# control-boardv1_0.net
KiCad netlist of a schematic drawn in Altium Designer
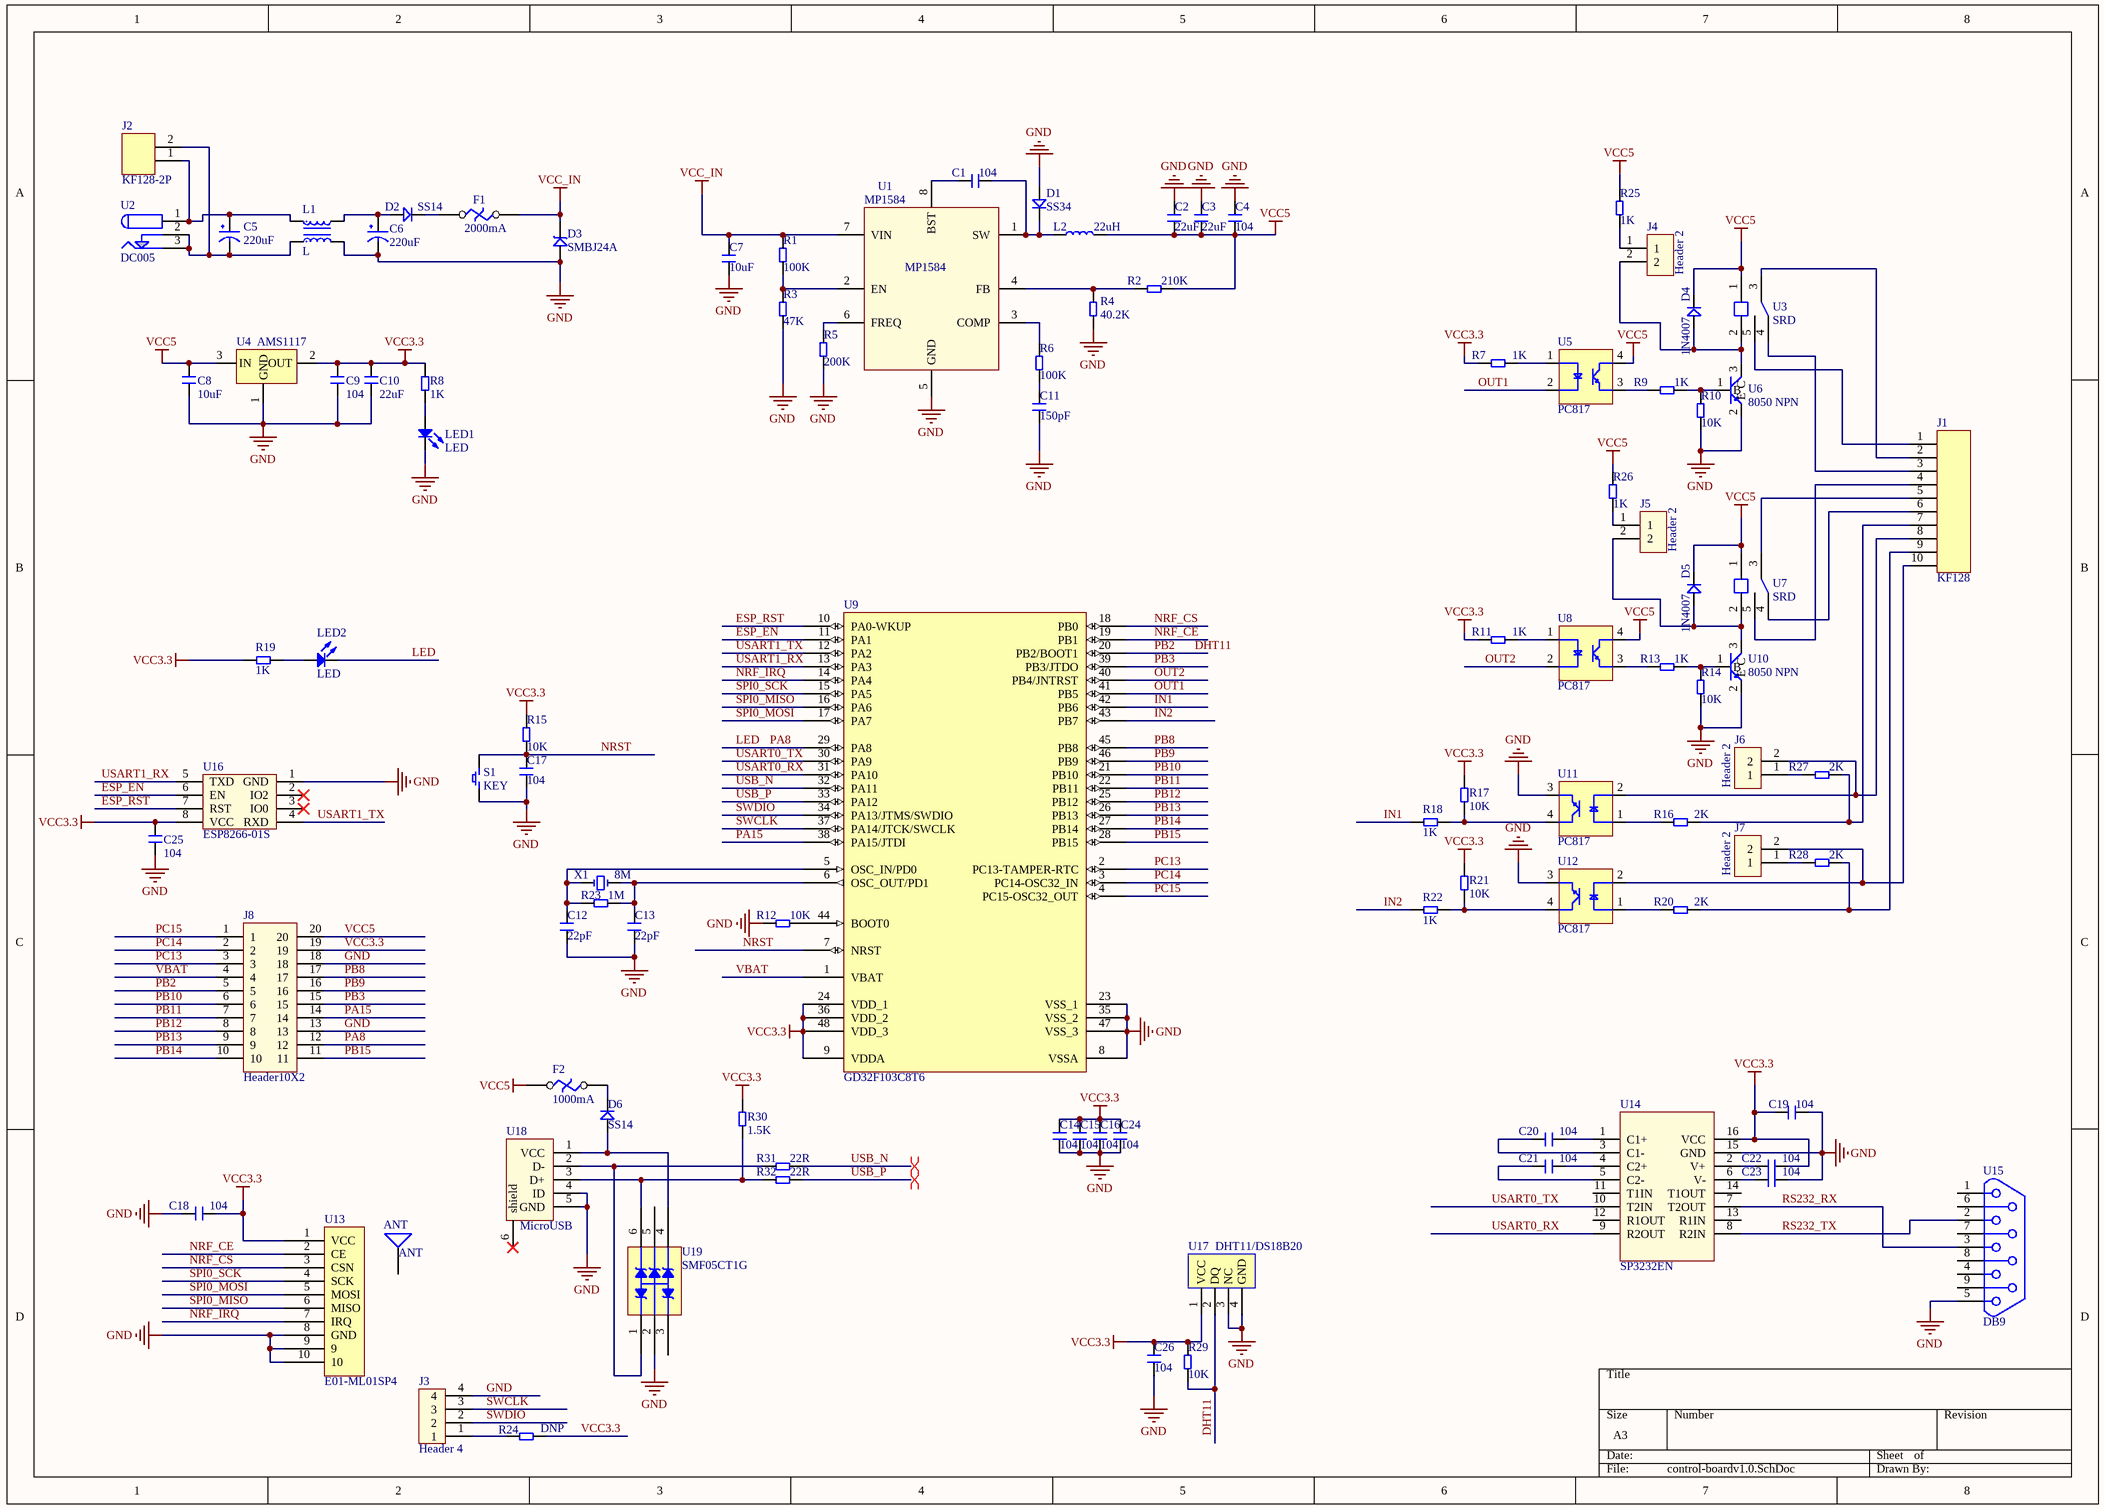
[diagram p0: control-boardv1.0.SchDoc]

(export (version "E")
  (design (tool "Eeschema 10.0.6"))
  (components
    (comp (ref "ANT") (value "ANT") (footprint "ANT-SMA-FR") (libsource (lib "squ-guiboard") (part "ANT")))
    (comp (ref "C1") (value "104") (footprint "C 0603") (libsource (lib "squ-guiboard") (part "CAP")))
    (comp (ref "C2") (value "22uF") (footprint "C 0805") (libsource (lib "squ-guiboard") (part "CAP")))
    (comp (ref "C3") (value "22uF") (footprint "C 0805") (libsource (lib "squ-guiboard") (part "CAP")))
    (comp (ref "C4") (value "104") (footprint "C 0603") (libsource (lib "squ-guiboard") (part "CAP")))
    (comp (ref "C5")
      (value "220uF")
      (footprint "CS 3.5*8*11.5 - C")
      (description "极性电容")
      (libsource (lib "squ-guiboard") (part "CAP Pol"))
    )
    (comp (ref "C6")
      (value "220uF")
      (footprint "CS 3.5*8*11.5 - C")
      (description "极性电容")
      (libsource (lib "squ-guiboard") (part "CAP Pol"))
    )
    (comp (ref "C7") (value "10uF") (footprint "C 0805") (libsource (lib "squ-guiboard") (part "CAP")))
    (comp (ref "C8") (value "10uF") (footprint "C 0805") (libsource (lib "squ-guiboard") (part "CAP")))
    (comp (ref "C9") (value "104") (footprint "C 0603") (libsource (lib "squ-guiboard") (part "CAP")))
    (comp (ref "C10") (value "22uF") (footprint "C 0805") (libsource (lib "squ-guiboard") (part "CAP")))
    (comp (ref "C11") (value "150pF") (footprint "C 0603") (libsource (lib "squ-guiboard") (part "CAP")))
    (comp (ref "C12") (value "22pF") (footprint "C 0603") (libsource (lib "squ-guiboard") (part "CAP")))
    (comp (ref "C13") (value "22pF") (footprint "C 0603") (libsource (lib "squ-guiboard") (part "CAP")))
    (comp (ref "C14") (value "104") (footprint "C 0603") (libsource (lib "squ-guiboard") (part "CAP")))
    (comp (ref "C15") (value "104") (footprint "C 0603") (libsource (lib "squ-guiboard") (part "CAP")))
    (comp (ref "C16") (value "104") (footprint "C 0603") (libsource (lib "squ-guiboard") (part "CAP")))
    (comp (ref "C17") (value "104") (footprint "C 0603") (libsource (lib "squ-guiboard") (part "CAP")))
    (comp (ref "C18") (value "104") (footprint "C 0603") (libsource (lib "squ-guiboard") (part "CAP")))
    (comp (ref "C19") (value "104") (footprint "C 0603") (libsource (lib "squ-guiboard") (part "CAP")))
    (comp (ref "C20") (value "104") (footprint "C 0603") (libsource (lib "squ-guiboard") (part "CAP")))
    (comp (ref "C21") (value "104") (footprint "C 0603") (libsource (lib "squ-guiboard") (part "CAP")))
    (comp (ref "C22") (value "104") (footprint "C 0603") (libsource (lib "squ-guiboard") (part "CAP")))
    (comp (ref "C23") (value "104") (footprint "C 0603") (libsource (lib "squ-guiboard") (part "CAP")))
    (comp (ref "C24") (value "104") (footprint "C 0603") (libsource (lib "squ-guiboard") (part "CAP")))
    (comp (ref "C25") (value "104") (footprint "C 0603") (libsource (lib "squ-guiboard") (part "CAP")))
    (comp (ref "C26") (value "104") (footprint "C 0603") (libsource (lib "squ-guiboard") (part "CAP")))
    (comp (ref "D1") (value "SS34") (footprint "SMA") (libsource (lib "squ-guiboard") (part "Diode")))
    (comp (ref "D2") (value "SS14") (footprint "SMA") (libsource (lib "squ-guiboard") (part "Diode")))
    (comp (ref "D3") (value "SMBJ24A") (footprint "SMA") (libsource (lib "squ-guiboard") (part "D Schottky")))
    (comp (ref "D4") (value "1N4007") (footprint "LL34") (libsource (lib "squ-guiboard") (part "Diode")))
    (comp (ref "D5") (value "1N4007") (footprint "LL34") (libsource (lib "squ-guiboard") (part "Diode")))
    (comp (ref "D6") (value "SS14") (footprint "SMA") (libsource (lib "squ-guiboard") (part "Diode")))
    (comp (ref "F1")
      (value "2000mA")
      (footprint "F 1206")
      (description "熔断开关")
      (libsource (lib "squ-guiboard") (part "F"))
    )
    (comp (ref "F2")
      (value "1000mA")
      (footprint "F 1206")
      (description "熔断开关")
      (libsource (lib "squ-guiboard") (part "F"))
    )
    (comp (ref "J1")
      (value "KF128")
      (footprint "KF128-5.08-10P")
      (libsource (lib "squ-guiboard") (part "KF128-10P"))
    )
    (comp (ref "J2")
      (value "KF128-2P")
      (footprint "KF128-5.08-2P")
      (libsource (lib "squ-guiboard") (part "KF128-2P"))
    )
    (comp (ref "J3")
      (value "Header 4")
      (footprint "XH2.54-LI-4P")
      (libsource (lib "squ-guiboard") (part "Header 4"))
    )
    (comp (ref "J4")
      (value "Header 2")
      (footprint "XH2.54-LI-2P")
      (libsource (lib "squ-guiboard") (part "Header 2"))
    )
    (comp (ref "J5")
      (value "Header 2")
      (footprint "XH2.54-LI-2P")
      (libsource (lib "squ-guiboard") (part "Header 2"))
    )
    (comp (ref "J6") (value "Header 2") (footprint "XH2.54-LI-2P") (libsource (lib "") (part "Header 2_1")))
    (comp (ref "J7") (value "Header 2") (footprint "XH2.54-LI-2P") (libsource (lib "") (part "Header 2_1")))
    (comp (ref "J8")
      (value "Header10X2")
      (footprint "HDR2.54-LI-2x10P")
      (libsource (lib "squ-guiboard") (part "Header10X2"))
    )
    (comp (ref "L1") (value "L") (footprint "L UU9.8") (libsource (lib "squ-guiboard") (part "L2")))
    (comp (ref "L2") (value "22uH") (footprint "L CDRH74") (libsource (lib "squ-guiboard") (part "L")))
    (comp (ref "LED1") (value "LED") (footprint "LED 3MM") (libsource (lib "squ-guiboard") (part "LED")))
    (comp (ref "LED2") (value "LED") (footprint "LED 3MM") (libsource (lib "squ-guiboard") (part "LED")))
    (comp (ref "R1") (value "100K") (footprint "R 0603") (libsource (lib "squ-guiboard") (part "RES")))
    (comp (ref "R2") (value "210K") (footprint "R 0603") (libsource (lib "squ-guiboard") (part "RES")))
    (comp (ref "R3") (value "47K") (footprint "R 0603") (libsource (lib "squ-guiboard") (part "RES")))
    (comp (ref "R4") (value "40.2K") (footprint "R 0603") (libsource (lib "squ-guiboard") (part "RES")))
    (comp (ref "R5") (value "200K") (footprint "R 0603") (libsource (lib "squ-guiboard") (part "RES")))
    (comp (ref "R6") (value "100K") (footprint "R 0603") (libsource (lib "squ-guiboard") (part "RES")))
    (comp (ref "R7") (value "1K") (footprint "R 0603") (libsource (lib "squ-guiboard") (part "RES")))
    (comp (ref "R8") (value "1K") (footprint "R 0603") (libsource (lib "squ-guiboard") (part "RES")))
    (comp (ref "R9") (value "1K") (footprint "R 0603") (libsource (lib "squ-guiboard") (part "RES")))
    (comp (ref "R10") (value "10K") (footprint "R 0603") (libsource (lib "squ-guiboard") (part "RES")))
    (comp (ref "R11") (value "1K") (footprint "R 0603") (libsource (lib "squ-guiboard") (part "RES")))
    (comp (ref "R12") (value "10K") (footprint "R 0603") (libsource (lib "squ-guiboard") (part "RES")))
    (comp (ref "R13") (value "1K") (footprint "R 0603") (libsource (lib "squ-guiboard") (part "RES")))
    (comp (ref "R14") (value "10K") (footprint "R 0603") (libsource (lib "squ-guiboard") (part "RES")))
    (comp (ref "R15") (value "10K") (footprint "R 0603") (libsource (lib "squ-guiboard") (part "RES")))
    (comp (ref "R16") (value "2K") (footprint "R 0603") (libsource (lib "squ-guiboard") (part "RES")))
    (comp (ref "R17") (value "10K") (footprint "R 0603") (libsource (lib "squ-guiboard") (part "RES")))
    (comp (ref "R18") (value "1K") (footprint "R 0603") (libsource (lib "squ-guiboard") (part "RES")))
    (comp (ref "R19") (value "1K") (footprint "R 0603") (libsource (lib "squ-guiboard") (part "RES")))
    (comp (ref "R20") (value "2K") (footprint "R 0603") (libsource (lib "squ-guiboard") (part "RES")))
    (comp (ref "R21") (value "10K") (footprint "R 0603") (libsource (lib "squ-guiboard") (part "RES")))
    (comp (ref "R22") (value "1K") (footprint "R 0603") (libsource (lib "squ-guiboard") (part "RES")))
    (comp (ref "R23") (value "1M") (footprint "R 0603") (libsource (lib "squ-guiboard") (part "RES")))
    (comp (ref "R24") (value "DNP") (footprint "R 0603") (libsource (lib "松鼠GUI原理图库") (part "RES")))
    (comp (ref "R25") (value "1K") (footprint "R 0603") (libsource (lib "squ-guiboard") (part "RES")))
    (comp (ref "R26") (value "1K") (footprint "R 0603") (libsource (lib "squ-guiboard") (part "RES")))
    (comp (ref "R27") (value "2K") (footprint "R 0603") (libsource (lib "squ-guiboard") (part "RES")))
    (comp (ref "R28") (value "2K") (footprint "R 0603") (libsource (lib "squ-guiboard") (part "RES")))
    (comp (ref "R29") (value "10K") (footprint "R 0603") (libsource (lib "squ-guiboard") (part "RES")))
    (comp (ref "R30") (value "1.5K") (footprint "R 0603") (libsource (lib "squ-guiboard") (part "RES")))
    (comp (ref "R31") (value "22R") (footprint "R 0603") (libsource (lib "squ-guiboard") (part "RES")))
    (comp (ref "R32") (value "22R") (footprint "R 0603") (libsource (lib "squ-guiboard") (part "RES")))
    (comp (ref "S1")
      (value "KEY")
      (footprint "KEY SMD-3*6*2.5")
      (libsource (lib "squ-guiboard") (part "KEY"))
    )
    (comp (ref "U1")
      (value "MP1584")
      (footprint "MP1584 SOP8")
      (description "DCDC芯片")
      (libsource (lib "squ-guiboard") (part "MP1584"))
    )
    (comp (ref "U2") (value "DC005") (footprint "DC005") (libsource (lib "squ-guiboard") (part "DC005")))
    (comp (ref "U3")
      (value "SRD")
      (footprint "SRD-C")
      (description "继电器")
      (libsource (lib "squ-guiboard") (part "SRD"))
    )
    (comp (ref "U4")
      (value "AMS1117")
      (footprint "SOT223")
      (description "LDO")
      (libsource (lib "squ-guiboard") (part "AMS1117"))
    )
    (comp (ref "U5")
      (value "PC817")
      (footprint "DIP4")
      (description "光耦")
      (libsource (lib "") (part "PC817_1"))
    )
    (comp (ref "U6") (value "8050 NPN") (footprint "SOT23-3") (libsource (lib "squ-guiboard") (part "NPN")))
    (comp (ref "U7")
      (value "SRD")
      (footprint "SRD-C")
      (description "继电器")
      (libsource (lib "squ-guiboard") (part "SRD"))
    )
    (comp (ref "U8")
      (value "PC817")
      (footprint "DIP4")
      (description "光耦")
      (libsource (lib "") (part "PC817_1"))
    )
    (comp (ref "U9")
      (value "GD32F103C8T6")
      (footprint "LQFP48")
      (libsource (lib "squ-guiboard") (part "GD32F103C8T6"))
    )
    (comp (ref "U10") (value "8050 NPN") (footprint "SOT23-3") (libsource (lib "squ-guiboard") (part "NPN")))
    (comp (ref "U11")
      (value "PC817")
      (footprint "DIP4")
      (description "光耦")
      (libsource (lib "squ-guiboard") (part "PC817"))
    )
    (comp (ref "U12")
      (value "PC817")
      (footprint "DIP4")
      (description "光耦")
      (libsource (lib "squ-guiboard") (part "PC817"))
    )
    (comp (ref "U13")
      (value "E01-ML01SP4")
      (footprint "E01-ML01SP4")
      (description "2.4G无限模块")
      (libsource (lib "squ-guiboard") (part "24L01"))
    )
    (comp (ref "U14")
      (value "SP3232EN")
      (footprint "TSSOP16")
      (libsource (lib "squ-guiboard") (part "SP3232EN"))
    )
    (comp (ref "U15") (value "DB9") (footprint "DB9-MALE") (libsource (lib "squ-guiboard") (part "DB9")))
    (comp (ref "U16")
      (value "ESP8266-01S")
      (footprint "ESP8266-01S")
      (description "WIFI模块")
      (libsource (lib "squ-guiboard") (part "ESP8266-01S"))
    )
    (comp (ref "U17")
      (value "DHT11/DS18B20")
      (footprint "DHT11")
      (libsource (lib "squ-guiboard") (part "DHT11"))
    )
    (comp (ref "U18")
      (value "MicroUSB")
      (footprint "USB MICROUSB-L")
      (libsource (lib "squ-guiboard") (part "MicroUSB"))
    )
    (comp (ref "U19")
      (value "SMF05CT1G")
      (footprint "LC-SC-70-6(SOT-363)")
      (description "TVS")
      (libsource (lib "Miscellaneous Devices LC") (part "SMF05CT1G"))
    )
    (comp (ref "X1") (value "8M") (footprint "XTAL-HC49S") (libsource (lib "squ-guiboard") (part "XTAL-2P")))
  )
  (nets
    (net (code "1") (name "/DHT11") (class "Default")
      (node (ref "J8") (pin "5") (pinfunction "5_5") (pintype "passive"))
      (node (ref "R29") (pin "1") (pintype "passive"))
      (node (ref "U17") (pin "2") (pinfunction "DQ_2") (pintype "passive"))
      (node (ref "U9") (pin "20") (pinfunction "PB2/BOOT1_20") (pintype "bidirectional"))
    )
    (net (code "2") (name "/ESP_EN") (class "Default")
      (node (ref "U16") (pin "6") (pinfunction "EN_6") (pintype "passive"))
      (node (ref "U9") (pin "11") (pinfunction "PA1_11") (pintype "bidirectional"))
    )
    (net (code "3") (name "/ESP_RST") (class "Default")
      (node (ref "U16") (pin "7") (pinfunction "RST_7") (pintype "passive"))
      (node (ref "U9") (pin "10") (pinfunction "PA0-WKUP_10") (pintype "bidirectional"))
    )
    (net (code "4") (name "/IN1") (class "Default")
      (node (ref "R18") (pin "1") (pintype "passive"))
      (node (ref "U9") (pin "42") (pinfunction "PB6_42") (pintype "bidirectional"))
    )
    (net (code "5") (name "/IN2") (class "Default")
      (node (ref "R22") (pin "1") (pintype "passive"))
      (node (ref "U9") (pin "43") (pinfunction "PB7_43") (pintype "bidirectional"))
    )
    (net (code "6") (name "/LED") (class "Default")
      (node (ref "J8") (pin "12") (pinfunction "12_12") (pintype "passive"))
      (node (ref "LED2") (pin "2") (pinfunction "K_2") (pintype "passive"))
      (node (ref "U9") (pin "29") (pinfunction "PA8_29") (pintype "bidirectional"))
    )
    (net (code "7") (name "/NRF_CE") (class "Default")
      (node (ref "U13") (pin "2") (pinfunction "CE_2") (pintype "passive"))
      (node (ref "U9") (pin "19") (pinfunction "PB1_19") (pintype "bidirectional"))
    )
    (net (code "8") (name "/NRF_CS") (class "Default")
      (node (ref "U13") (pin "3") (pinfunction "CSN_3") (pintype "passive"))
      (node (ref "U9") (pin "18") (pinfunction "PB0_18") (pintype "bidirectional"))
    )
    (net (code "9") (name "/NRF_IRQ") (class "Default")
      (node (ref "U13") (pin "7") (pinfunction "IRQ_7") (pintype "passive"))
      (node (ref "U9") (pin "14") (pinfunction "PA4_14") (pintype "bidirectional"))
    )
    (net (code "10") (name "/NRST") (class "Default")
      (node (ref "C17") (pin "2") (pinfunction "2_2") (pintype "passive"))
      (node (ref "R15") (pin "1") (pintype "passive"))
      (node (ref "S1") (pin "2") (pinfunction "2_2") (pintype "passive"))
      (node (ref "U9") (pin "7") (pinfunction "NRST_7") (pintype "bidirectional"))
    )
    (net (code "11") (name "/OUT1") (class "Default")
      (node (ref "U5") (pin "2") (pinfunction "2_2") (pintype "passive"))
      (node (ref "U9") (pin "41") (pinfunction "PB5_41") (pintype "bidirectional"))
    )
    (net (code "12") (name "/OUT2") (class "Default")
      (node (ref "U8") (pin "2") (pinfunction "2_2") (pintype "passive"))
      (node (ref "U9") (pin "40") (pinfunction "PB4/JNTRST_40") (pintype "bidirectional"))
    )
    (net (code "13") (name "/PA15") (class "Default")
      (node (ref "J8") (pin "14") (pinfunction "14_14") (pintype "passive"))
      (node (ref "U9") (pin "38") (pinfunction "PA15/JTDI_38") (pintype "bidirectional"))
    )
    (net (code "14") (name "/PB3") (class "Default")
      (node (ref "J8") (pin "15") (pinfunction "15_15") (pintype "passive"))
      (node (ref "U9") (pin "39") (pinfunction "PB3/JTDO_39") (pintype "bidirectional"))
    )
    (net (code "15") (name "/PB8") (class "Default")
      (node (ref "J8") (pin "17") (pinfunction "17_17") (pintype "passive"))
      (node (ref "U9") (pin "45") (pinfunction "PB8_45") (pintype "bidirectional"))
    )
    (net (code "16") (name "/PB9") (class "Default")
      (node (ref "J8") (pin "16") (pinfunction "16_16") (pintype "passive"))
      (node (ref "U9") (pin "46") (pinfunction "PB9_46") (pintype "bidirectional"))
    )
    (net (code "17") (name "/PB10") (class "Default")
      (node (ref "J8") (pin "6") (pinfunction "6_6") (pintype "passive"))
      (node (ref "U9") (pin "21") (pinfunction "PB10_21") (pintype "bidirectional"))
    )
    (net (code "18") (name "/PB11") (class "Default")
      (node (ref "J8") (pin "7") (pinfunction "7_7") (pintype "passive"))
      (node (ref "U9") (pin "22") (pinfunction "PB11_22") (pintype "bidirectional"))
    )
    (net (code "19") (name "/PB12") (class "Default")
      (node (ref "J8") (pin "8") (pinfunction "8_8") (pintype "passive"))
      (node (ref "U9") (pin "25") (pinfunction "PB12_25") (pintype "bidirectional"))
    )
    (net (code "20") (name "/PB13") (class "Default")
      (node (ref "J8") (pin "9") (pinfunction "9_9") (pintype "passive"))
      (node (ref "U9") (pin "26") (pinfunction "PB13_26") (pintype "bidirectional"))
    )
    (net (code "21") (name "/PB14") (class "Default")
      (node (ref "J8") (pin "10") (pinfunction "10_10") (pintype "passive"))
      (node (ref "U9") (pin "27") (pinfunction "PB14_27") (pintype "bidirectional"))
    )
    (net (code "22") (name "/PB15") (class "Default")
      (node (ref "J8") (pin "11") (pinfunction "11_11") (pintype "passive"))
      (node (ref "U9") (pin "28") (pinfunction "PB15_28") (pintype "bidirectional"))
    )
    (net (code "23") (name "/PC13") (class "Default")
      (node (ref "J8") (pin "3") (pinfunction "3_3") (pintype "passive"))
      (node (ref "U9") (pin "2") (pinfunction "PC13-TAMPER-RTC_2") (pintype "bidirectional"))
    )
    (net (code "24") (name "/PC14") (class "Default")
      (node (ref "J8") (pin "2") (pinfunction "2_2") (pintype "passive"))
      (node (ref "U9") (pin "3") (pinfunction "PC14-OSC32_IN_3") (pintype "bidirectional"))
    )
    (net (code "25") (name "/PC15") (class "Default")
      (node (ref "J8") (pin "1") (pinfunction "1_1") (pintype "passive"))
      (node (ref "U9") (pin "4") (pinfunction "PC15-OSC32_OUT_4") (pintype "bidirectional"))
    )
    (net (code "26") (name "/RS232_RX") (class "Default")
      (node (ref "U14") (pin "7") (pinfunction "T2OUT_7") (pintype "passive"))
      (node (ref "U15") (pin "3") (pinfunction "3_3") (pintype "passive"))
    )
    (net (code "27") (name "/RS232_TX") (class "Default")
      (node (ref "U14") (pin "8") (pinfunction "R2IN_8") (pintype "passive"))
      (node (ref "U15") (pin "2") (pinfunction "2_2") (pintype "passive"))
    )
    (net (code "28") (name "/SPI0_MISO") (class "Default")
      (node (ref "U13") (pin "6") (pinfunction "MISO_6") (pintype "passive"))
      (node (ref "U9") (pin "16") (pinfunction "PA6_16") (pintype "bidirectional"))
    )
    (net (code "29") (name "/SPI0_MOSI") (class "Default")
      (node (ref "U13") (pin "5") (pinfunction "MOSI_5") (pintype "passive"))
      (node (ref "U9") (pin "17") (pinfunction "PA7_17") (pintype "bidirectional"))
    )
    (net (code "30") (name "/SPI0_SCK") (class "Default")
      (node (ref "U13") (pin "4") (pinfunction "SCK_4") (pintype "passive"))
      (node (ref "U9") (pin "15") (pinfunction "PA5_15") (pintype "bidirectional"))
    )
    (net (code "31") (name "/SWCLK") (class "Default")
      (node (ref "J3") (pin "3") (pinfunction "3_3") (pintype "passive"))
      (node (ref "U9") (pin "37") (pinfunction "PA14/JTCK/SWCLK_37") (pintype "bidirectional"))
    )
    (net (code "32") (name "/SWDIO") (class "Default")
      (node (ref "J3") (pin "2") (pinfunction "2_2") (pintype "passive"))
      (node (ref "U9") (pin "34") (pinfunction "PA13/JTMS/SWDIO_34") (pintype "bidirectional"))
    )
    (net (code "33") (name "/USART0_RX") (class "Default")
      (node (ref "U14") (pin "9") (pinfunction "R2OUT_9") (pintype "passive"))
      (node (ref "U9") (pin "31") (pinfunction "PA10_31") (pintype "bidirectional"))
    )
    (net (code "34") (name "/USART0_TX") (class "Default")
      (node (ref "U14") (pin "10") (pinfunction "T2IN_10") (pintype "passive"))
      (node (ref "U9") (pin "30") (pinfunction "PA9_30") (pintype "bidirectional"))
    )
    (net (code "35") (name "/USART1_RX") (class "Default")
      (node (ref "U16") (pin "5") (pinfunction "TXD_5") (pintype "passive"))
      (node (ref "U9") (pin "13") (pinfunction "PA3_13") (pintype "bidirectional"))
    )
    (net (code "36") (name "/USART1_TX") (class "Default")
      (node (ref "U16") (pin "4") (pinfunction "RXD_4") (pintype "passive"))
      (node (ref "U9") (pin "12") (pinfunction "PA2_12") (pintype "bidirectional"))
    )
    (net (code "37") (name "/USB_N") (class "Default")
      (node (ref "R31") (pin "2") (pintype "passive"))
      (node (ref "U9") (pin "32") (pinfunction "PA11_32") (pintype "bidirectional"))
    )
    (net (code "38") (name "/USB_P") (class "Default")
      (node (ref "R32") (pin "2") (pintype "passive"))
      (node (ref "U9") (pin "33") (pinfunction "PA12_33") (pintype "bidirectional"))
    )
    (net (code "39") (name "/VBAT") (class "Default")
      (node (ref "J8") (pin "4") (pinfunction "4_4") (pintype "passive"))
      (node (ref "U9") (pin "1") (pinfunction "VBAT_1") (pintype "power_in"))
    )
    (net (code "40") (name "GND") (class "Default")
      (node (ref "C10") (pin "1") (pinfunction "1_1") (pintype "passive"))
      (node (ref "C11") (pin "1") (pinfunction "1_1") (pintype "passive"))
      (node (ref "C12") (pin "1") (pinfunction "1_1") (pintype "passive"))
      (node (ref "C13") (pin "1") (pinfunction "1_1") (pintype "passive"))
      (node (ref "C14") (pin "1") (pinfunction "1_1") (pintype "passive"))
      (node (ref "C15") (pin "1") (pinfunction "1_1") (pintype "passive"))
      (node (ref "C16") (pin "1") (pinfunction "1_1") (pintype "passive"))
      (node (ref "C17") (pin "1") (pinfunction "1_1") (pintype "passive"))
      (node (ref "C18") (pin "2") (pinfunction "2_2") (pintype "passive"))
      (node (ref "C19") (pin "1") (pinfunction "1_1") (pintype "passive"))
      (node (ref "C2") (pin "2") (pinfunction "2_2") (pintype "passive"))
      (node (ref "C23") (pin "2") (pinfunction "2_2") (pintype "passive"))
      (node (ref "C24") (pin "1") (pinfunction "1_1") (pintype "passive"))
      (node (ref "C25") (pin "2") (pinfunction "2_2") (pintype "passive"))
      (node (ref "C26") (pin "2") (pinfunction "2_2") (pintype "passive"))
      (node (ref "C3") (pin "2") (pinfunction "2_2") (pintype "passive"))
      (node (ref "C4") (pin "2") (pinfunction "2_2") (pintype "passive"))
      (node (ref "C6") (pin "2") (pinfunction "-_2") (pintype "passive"))
      (node (ref "C7") (pin "1") (pinfunction "1_1") (pintype "passive"))
      (node (ref "C8") (pin "1") (pinfunction "1_1") (pintype "passive"))
      (node (ref "C9") (pin "1") (pinfunction "1_1") (pintype "passive"))
      (node (ref "D1") (pin "1") (pintype "passive"))
      (node (ref "D3") (pin "1") (pintype "passive"))
      (node (ref "J3") (pin "4") (pinfunction "4_4") (pintype "passive"))
      (node (ref "J8") (pin "13") (pinfunction "13_13") (pintype "passive"))
      (node (ref "J8") (pin "18") (pinfunction "18_18") (pintype "passive"))
      (node (ref "L1") (pin "3") (pinfunction "3_3") (pintype "passive"))
      (node (ref "LED1") (pin "2") (pinfunction "K_2") (pintype "passive"))
      (node (ref "R10") (pin "1") (pintype "passive"))
      (node (ref "R12") (pin "1") (pintype "passive"))
      (node (ref "R14") (pin "1") (pintype "passive"))
      (node (ref "R3") (pin "1") (pintype "passive"))
      (node (ref "R4") (pin "1") (pintype "passive"))
      (node (ref "R5") (pin "1") (pintype "passive"))
      (node (ref "S1") (pin "1") (pinfunction "1_1") (pintype "passive"))
      (node (ref "U1") (pin "5") (pinfunction "GND_5") (pintype "passive"))
      (node (ref "U10") (pin "2") (pinfunction "E_2") (pintype "passive"))
      (node (ref "U11") (pin "3") (pinfunction "3_3") (pintype "passive"))
      (node (ref "U12") (pin "3") (pinfunction "3_3") (pintype "passive"))
      (node (ref "U13") (pin "10") (pinfunction "10_10") (pintype "passive"))
      (node (ref "U13") (pin "8") (pinfunction "GND_8") (pintype "passive"))
      (node (ref "U13") (pin "9") (pinfunction "9_9") (pintype "passive"))
      (node (ref "U14") (pin "15") (pinfunction "GND_15") (pintype "passive"))
      (node (ref "U15") (pin "5") (pinfunction "5_5") (pintype "passive"))
      (node (ref "U16") (pin "1") (pinfunction "GND_1") (pintype "passive"))
      (node (ref "U17") (pin "3") (pinfunction "NC_3") (pintype "passive"))
      (node (ref "U17") (pin "4") (pinfunction "GND_4") (pintype "passive"))
      (node (ref "U18") (pin "4") (pinfunction "ID_4") (pintype "passive"))
      (node (ref "U18") (pin "5") (pinfunction "GND_5") (pintype "passive"))
      (node (ref "U19") (pin "2") (pinfunction "2_2") (pintype "passive"))
      (node (ref "U4") (pin "1") (pinfunction "GND_1") (pintype "passive"))
      (node (ref "U6") (pin "2") (pinfunction "E_2") (pintype "passive"))
      (node (ref "U9") (pin "23") (pinfunction "VSS_1_23") (pintype "power_in"))
      (node (ref "U9") (pin "35") (pinfunction "VSS_2_35") (pintype "power_in"))
      (node (ref "U9") (pin "47") (pinfunction "VSS_3_47") (pintype "power_in"))
      (node (ref "U9") (pin "8") (pinfunction "VSSA_8") (pintype "power_in"))
    )
    (net (code "41") (name "Net-(C5-+)") (class "Default")
      (node (ref "C5") (pin "1") (pinfunction "+_1") (pintype "passive"))
      (node (ref "J2") (pin "1") (pinfunction "1_1") (pintype "passive"))
      (node (ref "L1") (pin "1") (pinfunction "1_1") (pintype "passive"))
      (node (ref "U2") (pin "1") (pintype "passive"))
    )
    (net (code "42") (name "Net-(C5--)") (class "Default")
      (node (ref "C5") (pin "2") (pinfunction "-_2") (pintype "passive"))
      (node (ref "J2") (pin "2") (pinfunction "2_2") (pintype "passive"))
      (node (ref "L1") (pin "4") (pinfunction "4_4") (pintype "passive"))
      (node (ref "U2") (pin "2") (pintype "passive"))
      (node (ref "U2") (pin "3") (pintype "passive"))
    )
    (net (code "43") (name "Net-(C6-+)") (class "Default")
      (node (ref "C6") (pin "1") (pinfunction "+_1") (pintype "passive"))
      (node (ref "D2") (pin "1") (pintype "passive"))
      (node (ref "L1") (pin "2") (pinfunction "2_2") (pintype "passive"))
    )
    (net (code "44") (name "Net-(C11-Pad2)") (class "Default")
      (node (ref "C11") (pin "2") (pinfunction "2_2") (pintype "passive"))
      (node (ref "R6") (pin "1") (pintype "passive"))
    )
    (net (code "45") (name "Net-(D2-Pad2)") (class "Default")
      (node (ref "D2") (pin "2") (pintype "passive"))
      (node (ref "F1") (pin "1") (pinfunction "1_1") (pintype "passive"))
    )
    (net (code "46") (name "Net-(D6-Pad2)") (class "Default")
      (node (ref "D6") (pin "2") (pintype "passive"))
      (node (ref "F2") (pin "1") (pinfunction "1_1") (pintype "passive"))
    )
    (net (code "47") (name "Net-(J1-Pad1)") (class "Default")
      (node (ref "J1") (pin "1") (pinfunction "1_1") (pintype "passive"))
      (node (ref "U3") (pin "5") (pintype "passive"))
    )
    (net (code "48") (name "Net-(J1-Pad2)") (class "Default")
      (node (ref "J1") (pin "2") (pinfunction "2_2") (pintype "passive"))
      (node (ref "U3") (pin "3") (pintype "passive"))
    )
    (net (code "49") (name "Net-(J1-Pad3)") (class "Default")
      (node (ref "J1") (pin "3") (pinfunction "3_3") (pintype "passive"))
      (node (ref "U3") (pin "4") (pintype "passive"))
    )
    (net (code "50") (name "Net-(J1-Pad4)") (class "Default")
      (node (ref "J1") (pin "4") (pinfunction "4_4") (pintype "passive"))
      (node (ref "U7") (pin "5") (pintype "passive"))
    )
    (net (code "51") (name "Net-(J1-Pad5)") (class "Default")
      (node (ref "J1") (pin "5") (pinfunction "5_5") (pintype "passive"))
      (node (ref "U7") (pin "3") (pintype "passive"))
    )
    (net (code "52") (name "Net-(J1-Pad6)") (class "Default")
      (node (ref "J1") (pin "6") (pinfunction "6_6") (pintype "passive"))
      (node (ref "U7") (pin "4") (pintype "passive"))
    )
    (net (code "53") (name "Net-(J1-Pad7)") (class "Default")
      (node (ref "J1") (pin "7") (pinfunction "7_7") (pintype "passive"))
      (node (ref "R16") (pin "2") (pintype "passive"))
      (node (ref "R27") (pin "2") (pintype "passive"))
    )
    (net (code "54") (name "Net-(J1-Pad8)") (class "Default")
      (node (ref "J1") (pin "8") (pinfunction "8_8") (pintype "passive"))
      (node (ref "J6") (pin "2") (pinfunction "2_2") (pintype "passive"))
      (node (ref "U11") (pin "2") (pinfunction "2_2") (pintype "passive"))
    )
    (net (code "55") (name "Net-(J1-Pad9)") (class "Default")
      (node (ref "J1") (pin "9") (pinfunction "9_9") (pintype "passive"))
      (node (ref "R20") (pin "2") (pintype "passive"))
      (node (ref "R28") (pin "2") (pintype "passive"))
    )
    (net (code "56") (name "Net-(J1-Pad10)") (class "Default")
      (node (ref "J1") (pin "10") (pinfunction "10_10") (pintype "passive"))
      (node (ref "J7") (pin "2") (pinfunction "2_2") (pintype "passive"))
      (node (ref "U12") (pin "2") (pinfunction "2_2") (pintype "passive"))
    )
    (net (code "57") (name "Net-(J3-Pad1)") (class "Default")
      (node (ref "J3") (pin "1") (pinfunction "1_1") (pintype "passive"))
      (node (ref "R24") (pin "1") (pintype "passive"))
    )
    (net (code "58") (name "Net-(J4-Pad1)") (class "Default")
      (node (ref "J4") (pin "1") (pinfunction "1_1") (pintype "passive"))
      (node (ref "R25") (pin "1") (pintype "passive"))
    )
    (net (code "59") (name "Net-(J5-Pad1)") (class "Default")
      (node (ref "J5") (pin "1") (pinfunction "1_1") (pintype "passive"))
      (node (ref "R26") (pin "1") (pintype "passive"))
    )
    (net (code "60") (name "Net-(J6-Pad1)") (class "Default")
      (node (ref "J6") (pin "1") (pinfunction "1_1") (pintype "passive"))
      (node (ref "R27") (pin "1") (pintype "passive"))
    )
    (net (code "61") (name "Net-(J7-Pad1)") (class "Default")
      (node (ref "J7") (pin "1") (pinfunction "1_1") (pintype "passive"))
      (node (ref "R28") (pin "1") (pintype "passive"))
    )
    (net (code "62") (name "Net-(LED1-A)") (class "Default")
      (node (ref "LED1") (pin "1") (pinfunction "A_1") (pintype "passive"))
      (node (ref "R8") (pin "1") (pintype "passive"))
    )
    (net (code "63") (name "Net-(LED2-A)") (class "Default")
      (node (ref "LED2") (pin "1") (pinfunction "A_1") (pintype "passive"))
      (node (ref "R19") (pin "1") (pintype "passive"))
    )
    (net (code "64") (name "Net-(R7-Pad2)") (class "Default")
      (node (ref "R7") (pin "2") (pintype "passive"))
      (node (ref "U5") (pin "1") (pinfunction "1_1") (pintype "passive"))
    )
    (net (code "65") (name "Net-(R9-Pad1)") (class "Default")
      (node (ref "R9") (pin "1") (pintype "passive"))
      (node (ref "U5") (pin "3") (pinfunction "3_3") (pintype "passive"))
    )
    (net (code "66") (name "Net-(R11-Pad2)") (class "Default")
      (node (ref "R11") (pin "2") (pintype "passive"))
      (node (ref "U8") (pin "1") (pinfunction "1_1") (pintype "passive"))
    )
    (net (code "67") (name "Net-(R13-Pad1)") (class "Default")
      (node (ref "R13") (pin "1") (pintype "passive"))
      (node (ref "U8") (pin "3") (pinfunction "3_3") (pintype "passive"))
    )
    (net (code "68") (name "Net-(R16-Pad1)") (class "Default")
      (node (ref "R16") (pin "1") (pintype "passive"))
      (node (ref "U11") (pin "1") (pinfunction "1_1") (pintype "passive"))
    )
    (net (code "69") (name "Net-(R17-Pad1)") (class "Default")
      (node (ref "R17") (pin "1") (pintype "passive"))
      (node (ref "R18") (pin "2") (pintype "passive"))
      (node (ref "U11") (pin "4") (pinfunction "4_4") (pintype "passive"))
    )
    (net (code "70") (name "Net-(R20-Pad1)") (class "Default")
      (node (ref "R20") (pin "1") (pintype "passive"))
      (node (ref "U12") (pin "1") (pinfunction "1_1") (pintype "passive"))
    )
    (net (code "71") (name "Net-(R21-Pad1)") (class "Default")
      (node (ref "R21") (pin "1") (pintype "passive"))
      (node (ref "R22") (pin "2") (pintype "passive"))
      (node (ref "U12") (pin "4") (pinfunction "4_4") (pintype "passive"))
    )
    (net (code "72") (name "Net-(U1-BST)") (class "Default")
      (node (ref "C1") (pin "2") (pinfunction "2_2") (pintype "passive"))
      (node (ref "U1") (pin "8") (pinfunction "BST_8") (pintype "passive"))
    )
    (net (code "73") (name "Net-(U1-COMP)") (class "Default")
      (node (ref "R6") (pin "2") (pintype "passive"))
      (node (ref "U1") (pin "3") (pinfunction "COMP_3") (pintype "passive"))
    )
    (net (code "74") (name "Net-(U1-EN)") (class "Default")
      (node (ref "R1") (pin "1") (pintype "passive"))
      (node (ref "R3") (pin "2") (pintype "passive"))
      (node (ref "U1") (pin "2") (pinfunction "EN_2") (pintype "passive"))
    )
    (net (code "75") (name "Net-(U1-FB)") (class "Default")
      (node (ref "R2") (pin "1") (pintype "passive"))
      (node (ref "R4") (pin "2") (pintype "passive"))
      (node (ref "U1") (pin "4") (pinfunction "FB_4") (pintype "passive"))
    )
    (net (code "76") (name "Net-(U1-FREQ)") (class "Default")
      (node (ref "R5") (pin "2") (pintype "passive"))
      (node (ref "U1") (pin "6") (pinfunction "FREQ_6") (pintype "passive"))
    )
    (net (code "77") (name "Net-(U1-SW)") (class "Default")
      (node (ref "C1") (pin "1") (pinfunction "1_1") (pintype "passive"))
      (node (ref "D1") (pin "2") (pintype "passive"))
      (node (ref "L2") (pin "2") (pinfunction "2_2") (pintype "passive"))
      (node (ref "U1") (pin "1") (pinfunction "SW_1") (pintype "passive"))
    )
    (net (code "78") (name "Net-(U6-B)") (class "Default")
      (node (ref "R10") (pin "2") (pintype "passive"))
      (node (ref "R9") (pin "2") (pintype "passive"))
      (node (ref "U6") (pin "1") (pinfunction "B_1") (pintype "passive"))
    )
    (net (code "79") (name "Net-(U6-C)") (class "Default")
      (node (ref "D4") (pin "1") (pintype "passive"))
      (node (ref "J4") (pin "2") (pinfunction "2_2") (pintype "passive"))
      (node (ref "U3") (pin "2") (pintype "passive"))
      (node (ref "U6") (pin "3") (pinfunction "C_3") (pintype "passive"))
    )
    (net (code "80") (name "Net-(U9-BOOT0)") (class "Default")
      (node (ref "R12") (pin "2") (pintype "passive"))
      (node (ref "U9") (pin "44") (pinfunction "BOOT0_44") (pintype "input"))
    )
    (net (code "81") (name "Net-(U9-OSC_IN{slash}PD0)") (class "Default")
      (node (ref "C12") (pin "2") (pinfunction "2_2") (pintype "passive"))
      (node (ref "R23") (pin "2") (pintype "passive"))
      (node (ref "U9") (pin "5") (pinfunction "OSC_IN/PD0_5") (pintype "input"))
      (node (ref "X1") (pin "1") (pinfunction "1_1") (pintype "passive"))
    )
    (net (code "82") (name "Net-(U9-OSC_OUT{slash}PD1)") (class "Default")
      (node (ref "C13") (pin "2") (pinfunction "2_2") (pintype "passive"))
      (node (ref "R23") (pin "1") (pintype "passive"))
      (node (ref "U9") (pin "6") (pinfunction "OSC_OUT/PD1_6") (pintype "output"))
      (node (ref "X1") (pin "2") (pinfunction "2_2") (pintype "passive"))
    )
    (net (code "83") (name "Net-(U10-B)") (class "Default")
      (node (ref "R13") (pin "2") (pintype "passive"))
      (node (ref "R14") (pin "2") (pintype "passive"))
      (node (ref "U10") (pin "1") (pinfunction "B_1") (pintype "passive"))
    )
    (net (code "84") (name "Net-(U10-C)") (class "Default")
      (node (ref "D5") (pin "1") (pintype "passive"))
      (node (ref "J5") (pin "2") (pinfunction "2_2") (pintype "passive"))
      (node (ref "U10") (pin "3") (pinfunction "C_3") (pintype "passive"))
      (node (ref "U7") (pin "2") (pintype "passive"))
    )
    (net (code "85") (name "Net-(U14-C1+)") (class "Default")
      (node (ref "C20") (pin "2") (pinfunction "2_2") (pintype "passive"))
      (node (ref "U14") (pin "1") (pinfunction "C1+_1") (pintype "passive"))
    )
    (net (code "86") (name "Net-(U14-C1-)") (class "Default")
      (node (ref "C20") (pin "1") (pinfunction "1_1") (pintype "passive"))
      (node (ref "U14") (pin "3") (pinfunction "C1-_3") (pintype "passive"))
    )
    (net (code "87") (name "Net-(U14-C2+)") (class "Default")
      (node (ref "C21") (pin "2") (pinfunction "2_2") (pintype "passive"))
      (node (ref "U14") (pin "4") (pinfunction "C2+_4") (pintype "passive"))
    )
    (net (code "88") (name "Net-(U14-C2-)") (class "Default")
      (node (ref "C21") (pin "1") (pinfunction "1_1") (pintype "passive"))
      (node (ref "U14") (pin "5") (pinfunction "C2-_5") (pintype "passive"))
    )
    (net (code "89") (name "Net-(U14-V+)") (class "Default")
      (node (ref "C22") (pin "1") (pinfunction "1_1") (pintype "passive"))
      (node (ref "U14") (pin "2") (pinfunction "V+_2") (pintype "passive"))
    )
    (net (code "90") (name "Net-(U14-V-)") (class "Default")
      (node (ref "C23") (pin "1") (pinfunction "1_1") (pintype "passive"))
      (node (ref "U14") (pin "6") (pinfunction "V-_6") (pintype "passive"))
    )
    (net (code "91") (name "Net-(U18-D+)") (class "Default")
      (node (ref "R30") (pin "1") (pintype "passive"))
      (node (ref "R32") (pin "1") (pintype "passive"))
      (node (ref "U18") (pin "3") (pinfunction "D+_3") (pintype "passive"))
      (node (ref "U19") (pin "6") (pinfunction "6_6") (pintype "passive"))
    )
    (net (code "92") (name "Net-(U18-D-)") (class "Default")
      (node (ref "R31") (pin "1") (pintype "passive"))
      (node (ref "U18") (pin "2") (pinfunction "D-_2") (pintype "passive"))
      (node (ref "U19") (pin "1") (pinfunction "1_1") (pintype "passive"))
    )
    (net (code "93") (name "Net-(U18-VCC)") (class "Default")
      (node (ref "D6") (pin "1") (pintype "passive"))
      (node (ref "U18") (pin "1") (pinfunction "VCC_1") (pintype "passive"))
      (node (ref "U19") (pin "4") (pinfunction "4_4") (pintype "passive"))
    )
    (net (code "94") (name "VCC3.3") (class "Default")
      (node (ref "C10") (pin "2") (pinfunction "2_2") (pintype "passive"))
      (node (ref "C14") (pin "2") (pinfunction "2_2") (pintype "passive"))
      (node (ref "C15") (pin "2") (pinfunction "2_2") (pintype "passive"))
      (node (ref "C16") (pin "2") (pinfunction "2_2") (pintype "passive"))
      (node (ref "C18") (pin "1") (pinfunction "1_1") (pintype "passive"))
      (node (ref "C19") (pin "2") (pinfunction "2_2") (pintype "passive"))
      (node (ref "C22") (pin "2") (pinfunction "2_2") (pintype "passive"))
      (node (ref "C24") (pin "2") (pinfunction "2_2") (pintype "passive"))
      (node (ref "C25") (pin "1") (pinfunction "1_1") (pintype "passive"))
      (node (ref "C26") (pin "1") (pinfunction "1_1") (pintype "passive"))
      (node (ref "C9") (pin "2") (pinfunction "2_2") (pintype "passive"))
      (node (ref "J8") (pin "19") (pinfunction "19_19") (pintype "passive"))
      (node (ref "R11") (pin "1") (pintype "passive"))
      (node (ref "R15") (pin "2") (pintype "passive"))
      (node (ref "R17") (pin "2") (pintype "passive"))
      (node (ref "R19") (pin "2") (pintype "passive"))
      (node (ref "R21") (pin "2") (pintype "passive"))
      (node (ref "R24") (pin "2") (pintype "passive"))
      (node (ref "R29") (pin "2") (pintype "passive"))
      (node (ref "R30") (pin "2") (pintype "passive"))
      (node (ref "R7") (pin "1") (pintype "passive"))
      (node (ref "R8") (pin "2") (pintype "passive"))
      (node (ref "U13") (pin "1") (pinfunction "VCC_1") (pintype "passive"))
      (node (ref "U14") (pin "16") (pinfunction "VCC_16") (pintype "passive"))
      (node (ref "U16") (pin "8") (pinfunction "VCC_8") (pintype "passive"))
      (node (ref "U17") (pin "1") (pinfunction "VCC_1") (pintype "passive"))
      (node (ref "U4") (pin "2") (pinfunction "OUT_2") (pintype "passive"))
      (node (ref "U9") (pin "24") (pinfunction "VDD_1_24") (pintype "power_in"))
      (node (ref "U9") (pin "36") (pinfunction "VDD_2_36") (pintype "power_in"))
      (node (ref "U9") (pin "48") (pinfunction "VDD_3_48") (pintype "power_in"))
      (node (ref "U9") (pin "9") (pinfunction "VDDA_9") (pintype "power_in"))
    )
    (net (code "95") (name "VCC5") (class "Default")
      (node (ref "C2") (pin "1") (pinfunction "1_1") (pintype "passive"))
      (node (ref "C3") (pin "1") (pinfunction "1_1") (pintype "passive"))
      (node (ref "C4") (pin "1") (pinfunction "1_1") (pintype "passive"))
      (node (ref "C8") (pin "2") (pinfunction "2_2") (pintype "passive"))
      (node (ref "D4") (pin "2") (pintype "passive"))
      (node (ref "D5") (pin "2") (pintype "passive"))
      (node (ref "F2") (pin "2") (pinfunction "2_2") (pintype "passive"))
      (node (ref "J8") (pin "20") (pinfunction "20_20") (pintype "passive"))
      (node (ref "L2") (pin "1") (pinfunction "1_1") (pintype "passive"))
      (node (ref "R2") (pin "2") (pintype "passive"))
      (node (ref "R25") (pin "2") (pintype "passive"))
      (node (ref "R26") (pin "2") (pintype "passive"))
      (node (ref "U3") (pin "1") (pintype "passive"))
      (node (ref "U4") (pin "3") (pinfunction "IN_3") (pintype "passive"))
      (node (ref "U5") (pin "4") (pinfunction "4_4") (pintype "passive"))
      (node (ref "U7") (pin "1") (pintype "passive"))
      (node (ref "U8") (pin "4") (pinfunction "4_4") (pintype "passive"))
    )
    (net (code "96") (name "VCC_IN") (class "Default")
      (node (ref "C7") (pin "2") (pinfunction "2_2") (pintype "passive"))
      (node (ref "D3") (pin "2") (pintype "passive"))
      (node (ref "F1") (pin "2") (pinfunction "2_2") (pintype "passive"))
      (node (ref "R1") (pin "2") (pintype "passive"))
      (node (ref "U1") (pin "7") (pinfunction "VIN_7") (pintype "passive"))
    )
    (net (code "97") (name "unconnected-(ANT-Pad1)") (class "Default")
      (node (ref "ANT") (pin "1") (pinfunction "1_1") (pintype "passive"))
    )
    (net (code "98") (name "unconnected-(U14-R1IN-Pad13)") (class "Default")
      (node (ref "U14") (pin "13") (pinfunction "R1IN_13") (pintype "passive"))
    )
    (net (code "99") (name "unconnected-(U14-R1OUT-Pad12)") (class "Default")
      (node (ref "U14") (pin "12") (pinfunction "R1OUT_12") (pintype "passive"))
    )
    (net (code "100") (name "unconnected-(U14-T1IN-Pad11)") (class "Default")
      (node (ref "U14") (pin "11") (pinfunction "T1IN_11") (pintype "passive"))
    )
    (net (code "101") (name "unconnected-(U14-T1OUT-Pad14)") (class "Default")
      (node (ref "U14") (pin "14") (pinfunction "T1OUT_14") (pintype "passive"))
    )
    (net (code "102") (name "unconnected-(U15-Pad1)") (class "Default")
      (node (ref "U15") (pin "1") (pinfunction "1_1") (pintype "passive"))
    )
    (net (code "103") (name "unconnected-(U15-Pad4)") (class "Default")
      (node (ref "U15") (pin "4") (pinfunction "4_4") (pintype "passive"))
    )
    (net (code "104") (name "unconnected-(U15-Pad6)") (class "Default")
      (node (ref "U15") (pin "6") (pinfunction "6_6") (pintype "passive"))
    )
    (net (code "105") (name "unconnected-(U15-Pad7)") (class "Default")
      (node (ref "U15") (pin "7") (pinfunction "7_7") (pintype "passive"))
    )
    (net (code "106") (name "unconnected-(U15-Pad8)") (class "Default")
      (node (ref "U15") (pin "8") (pinfunction "8_8") (pintype "passive"))
    )
    (net (code "107") (name "unconnected-(U15-Pad9)") (class "Default")
      (node (ref "U15") (pin "9") (pinfunction "9_9") (pintype "passive"))
    )
    (net (code "108") (name "unconnected-(U16-IO0-Pad3)") (class "Default")
      (node (ref "U16") (pin "3") (pinfunction "IO0_3") (pintype "passive+no_connect"))
    )
    (net (code "109") (name "unconnected-(U16-IO2-Pad2)") (class "Default")
      (node (ref "U16") (pin "2") (pinfunction "IO2_2") (pintype "passive+no_connect"))
    )
    (net (code "110") (name "unconnected-(U18-shield-Pad6)") (class "Default")
      (node (ref "U18") (pin "6") (pinfunction "shield_6") (pintype "passive+no_connect"))
    )
    (net (code "111") (name "unconnected-(U19-Pad3)") (class "Default")
      (node (ref "U19") (pin "3") (pinfunction "3_3") (pintype "passive"))
    )
    (net (code "112") (name "unconnected-(U19-Pad5)") (class "Default")
      (node (ref "U19") (pin "5") (pinfunction "5_5") (pintype "passive"))
    )
  )
)
